# EasyEDA_Bench_2021-02-24.net
KiCad netlist of a schematic drawn in EasyEDA
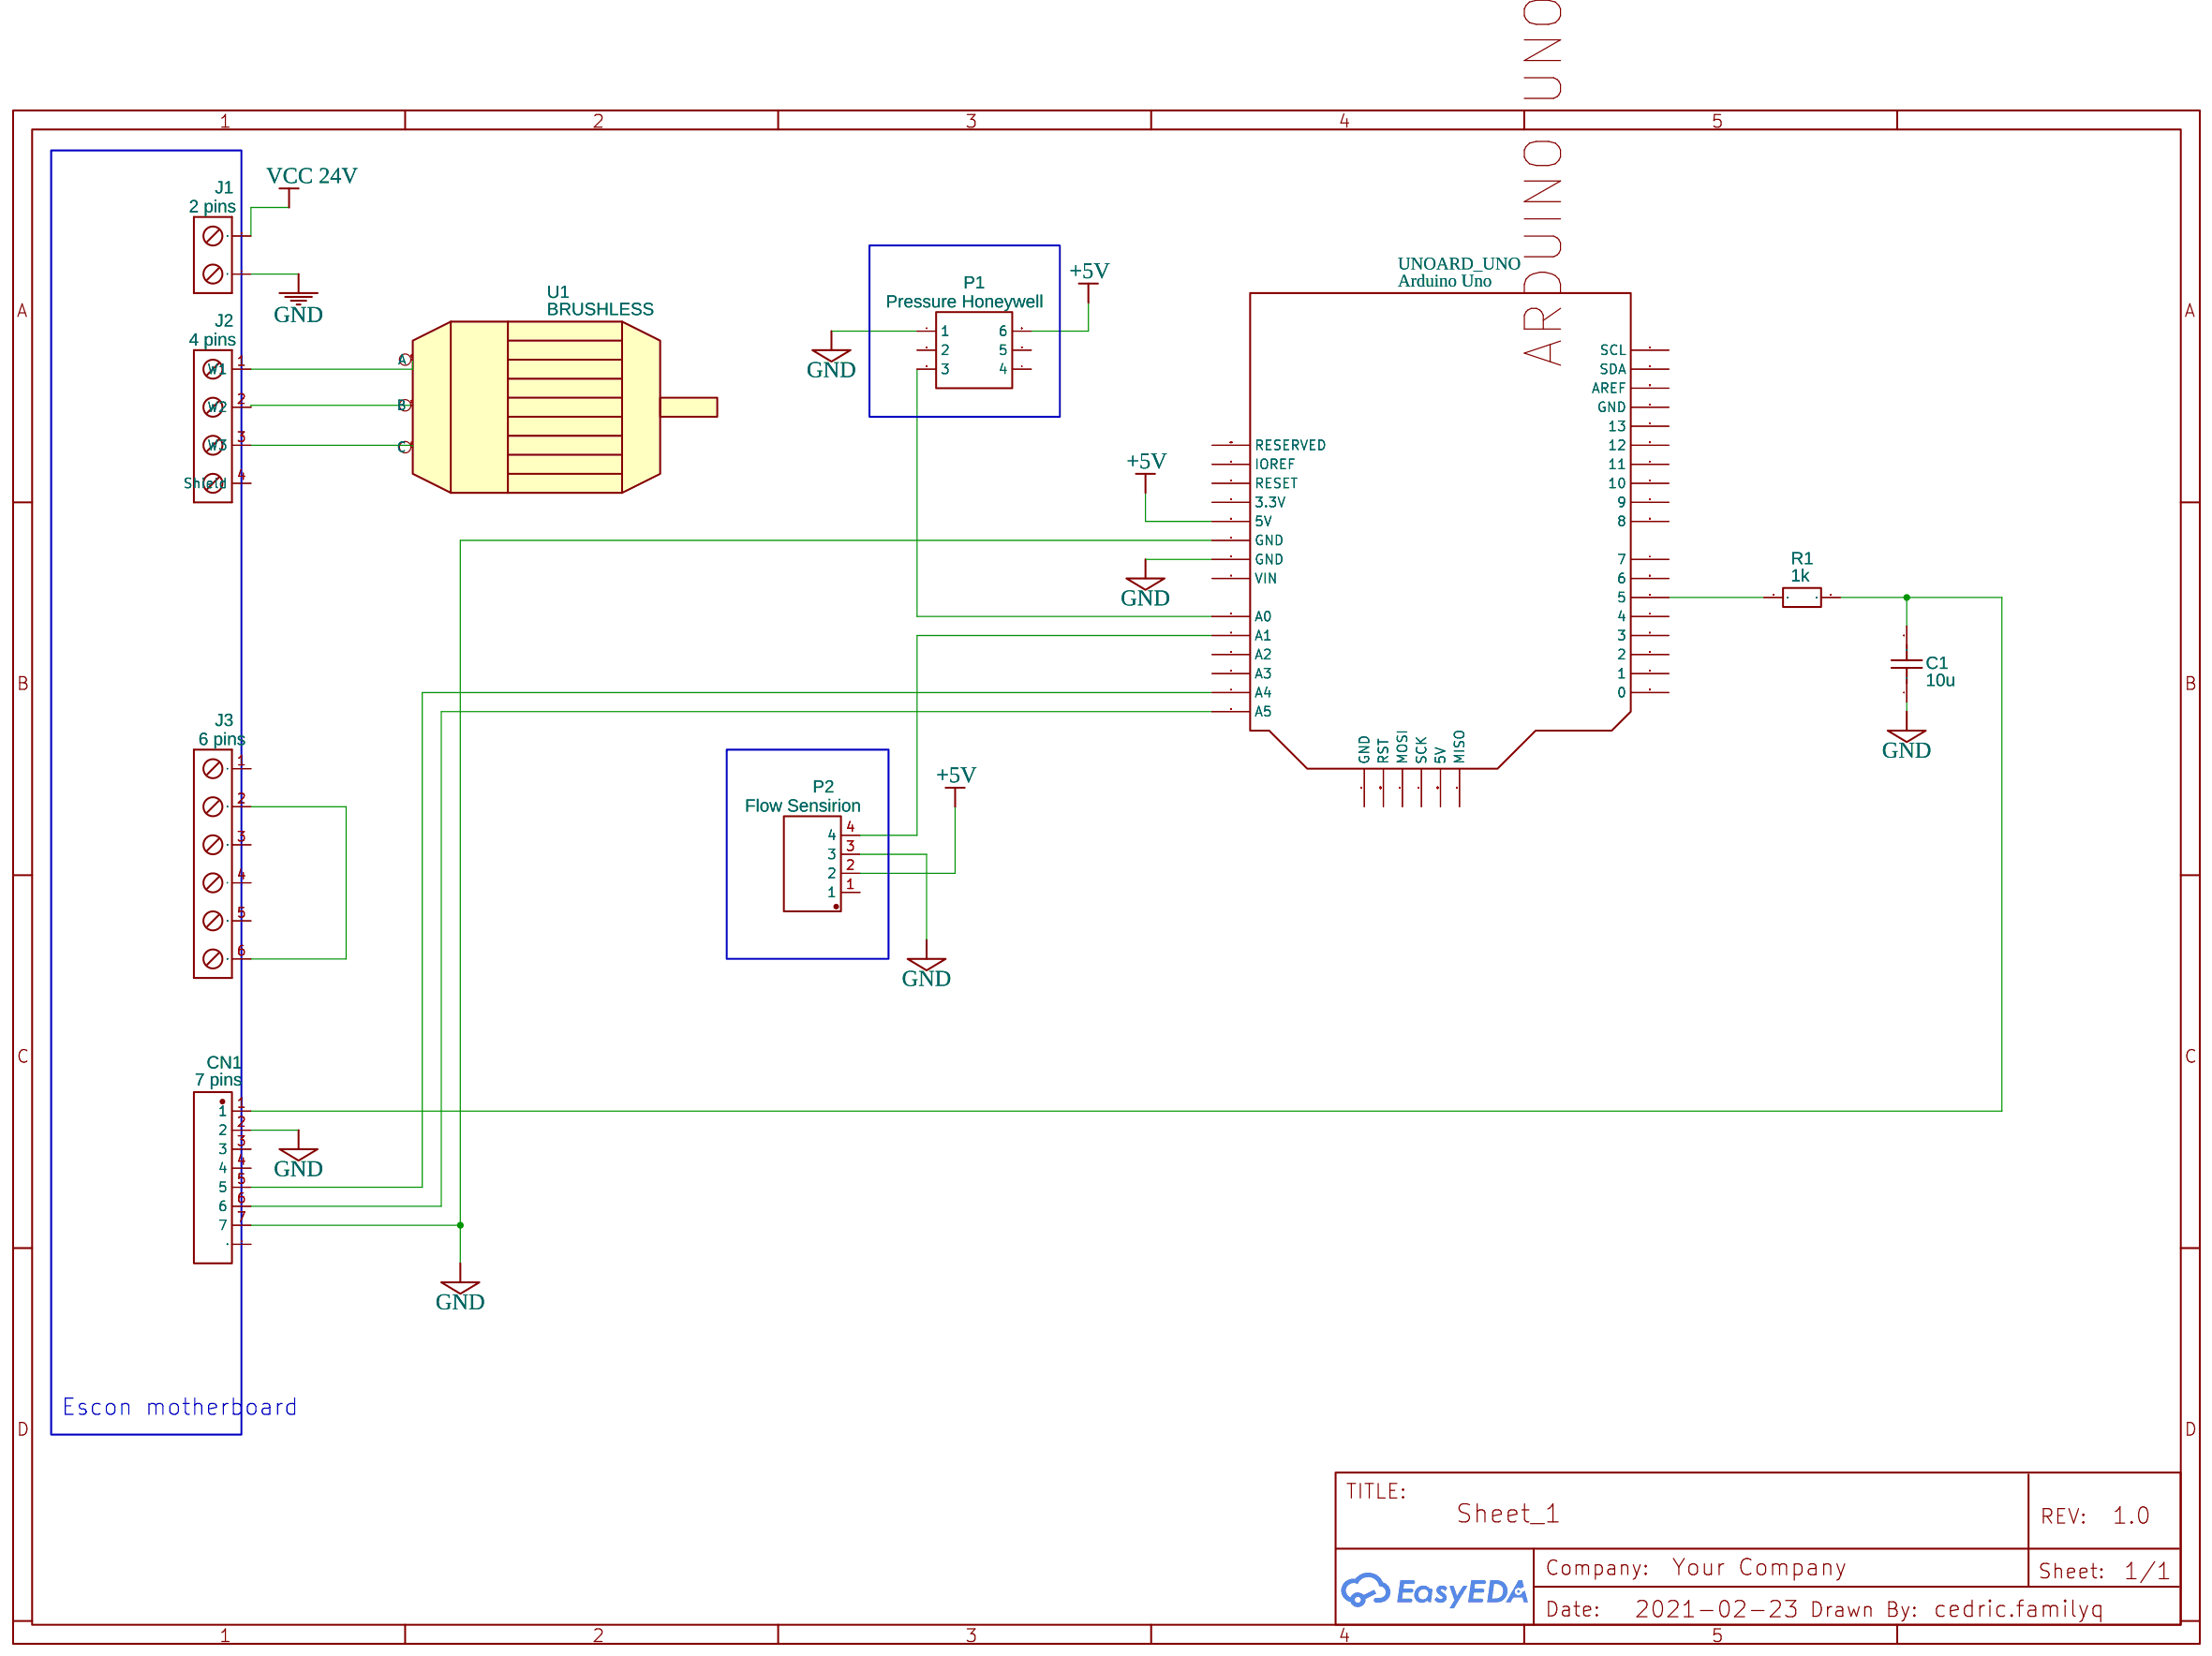
[diagram p0: schematic sheet]

(export (version "E")
  (design (tool "Eeschema 10.0.6"))
  (components
    (comp (ref "C1") (value "10u") (libsource (lib "") (part "C_0603_US")))
    (comp (ref "CN1")
      (value "7 pins")
      (fields
        (field (name "BOM_Manufacturer Part") "B2541CW-8P")
        (field (name "BOM_Supplier Part") "C339803")
      )
      (libsource (lib "") (part "B2541CW-8P"))
    )
    (comp (ref "J1")
      (value "2 pins")
      (fields (field (name "BOM_Manufacturer Part") "?") (field (name "BOM_Supplier Part") "320110031"))
      (libsource (lib "") (part "BORNIER-VIS v2"))
    )
    (comp (ref "J2")
      (value "4 pins")
      (fields (field (name "BOM_Manufacturer Part") "?") (field (name "BOM_Supplier Part") "320110031"))
      (libsource (lib "") (part "BORNIER-VIS-GREEN(4P-5.0)"))
    )
    (comp (ref "J3")
      (value "6 pins")
      (fields (field (name "BOM_Manufacturer Part") "?") (field (name "BOM_Supplier Part") "320110031"))
      (libsource (lib "") (part "BORNIER-VIS-GREEN(6P-5.0)"))
    )
    (comp (ref "P1")
      (value "Pressure Honeywell")
      (fields
        (field (name "BOM_Manufacturer Part") "2X3 2.54mm IDC Box")
        (field (name "BOM_Supplier Part") "C11214")
      )
      (libsource (lib "") (part "HDR-IDC-2.54-2X3P"))
    )
    (comp (ref "P2")
      (value "Flow Sensirion")
      (fields
        (field (name "BOM_Manufacturer Part") "210S-1*4P L=11.6MMGold-plated black")
        (field (name "BOM_Supplier Part") "C124378")
      )
      (libsource (lib "") (part "Header-Male-2.54_1x4_C124378"))
    )
    (comp (ref "R1") (value "1k") (libsource (lib "") (part "R_0603_EU")))
    (comp (ref "U1") (value "BRUSHLESS") (libsource (lib "") (part "BRUSHLESS")))
    (comp (ref "UNOARD_UNO") (value "Arduino Uno") (libsource (lib "") (part "Unknown_750_-570")))
  )
  (nets
    (net (code "1") (name "+5V") (class "Default")
      (node (ref "P1") (pin "6") (pinfunction "6_6") (pintype "unspecified"))
      (node (ref "P2") (pin "2") (pinfunction "2_2") (pintype "unspecified"))
      (node (ref "UNOARD_UNO") (pin "5V") (pinfunction "5V_5V") (pintype "passive"))
    )
    (net (code "2") (name "GND") (class "Default")
      (node (ref "C1") (pin "1") (pinfunction "1_1") (pintype "unspecified"))
      (node (ref "CN1") (pin "2") (pinfunction "2_2") (pintype "unspecified"))
      (node (ref "CN1") (pin "7") (pinfunction "7_7") (pintype "unspecified"))
      (node (ref "J1") (pin "1") (pinfunction "1_1") (pintype "unspecified"))
      (node (ref "P1") (pin "1") (pinfunction "1_1") (pintype "unspecified"))
      (node (ref "P2") (pin "3") (pinfunction "3_3") (pintype "unspecified"))
      (node (ref "UNOARD_UNO") (pin "GND") (pinfunction "GND_GND") (pintype "passive"))
    )
    (net (code "3") (name "Net-(C1-Pad2)") (class "Default")
      (node (ref "C1") (pin "2") (pinfunction "2_2") (pintype "unspecified"))
      (node (ref "CN1") (pin "1") (pinfunction "1_1") (pintype "unspecified"))
      (node (ref "R1") (pin "2") (pinfunction "2_2") (pintype "unspecified"))
    )
    (net (code "4") (name "Net-(CN1-Pad5)") (class "Default")
      (node (ref "CN1") (pin "5") (pinfunction "5_5") (pintype "unspecified"))
      (node (ref "UNOARD_UNO") (pin "A4") (pinfunction "A4_A4") (pintype "bidirectional"))
    )
    (net (code "5") (name "Net-(CN1-Pad6)") (class "Default")
      (node (ref "CN1") (pin "6") (pinfunction "6_6") (pintype "unspecified"))
      (node (ref "UNOARD_UNO") (pin "A5") (pinfunction "A5_A5") (pintype "bidirectional"))
    )
    (net (code "6") (name "Net-(J2-W1)") (class "Default")
      (node (ref "J2") (pin "1") (pinfunction "W1_1") (pintype "unspecified"))
      (node (ref "U1") (pin "1") (pinfunction "A_1") (pintype "unspecified"))
    )
    (net (code "7") (name "Net-(J2-W2)") (class "Default")
      (node (ref "J2") (pin "2") (pinfunction "W2_2") (pintype "unspecified"))
      (node (ref "U1") (pin "2") (pinfunction "B_2") (pintype "unspecified"))
    )
    (net (code "8") (name "Net-(J2-W3)") (class "Default")
      (node (ref "J2") (pin "3") (pinfunction "W3_3") (pintype "unspecified"))
      (node (ref "U1") (pin "3") (pinfunction "C_3") (pintype "unspecified"))
    )
    (net (code "9") (name "Net-(J3-Pad2)") (class "Default")
      (node (ref "J3") (pin "2") (pinfunction "2_2") (pintype "unspecified"))
      (node (ref "J3") (pin "6") (pinfunction "6_6") (pintype "unspecified"))
    )
    (net (code "10") (name "Net-(P1-Pad3)") (class "Default")
      (node (ref "P1") (pin "3") (pinfunction "3_3") (pintype "unspecified"))
      (node (ref "UNOARD_UNO") (pin "A0") (pinfunction "A0_A0") (pintype "bidirectional"))
    )
    (net (code "11") (name "Net-(P2-Pad4)") (class "Default")
      (node (ref "P2") (pin "4") (pinfunction "4_4") (pintype "unspecified"))
      (node (ref "UNOARD_UNO") (pin "A1") (pinfunction "A1_A1") (pintype "bidirectional"))
    )
    (net (code "12") (name "Net-(R1-Pad1)") (class "Default")
      (node (ref "R1") (pin "1") (pinfunction "1_1") (pintype "unspecified"))
      (node (ref "UNOARD_UNO") (pin "5") (pinfunction "5_5") (pintype "bidirectional"))
    )
    (net (code "13") (name "VCC 24V") (class "Default")
      (node (ref "J1") (pin "2") (pinfunction "2_2") (pintype "unspecified"))
    )
    (net (code "14") (name "unconnected-(CN1-Pad3)") (class "Default")
      (node (ref "CN1") (pin "3") (pinfunction "3_3") (pintype "unspecified"))
    )
    (net (code "15") (name "unconnected-(CN1-Pad4)") (class "Default")
      (node (ref "CN1") (pin "4") (pinfunction "4_4") (pintype "unspecified"))
    )
    (net (code "16") (name "unconnected-(CN1-Pad8)") (class "Default")
      (node (ref "CN1") (pin "8") (pinfunction "8_8") (pintype "unspecified"))
    )
    (net (code "17") (name "unconnected-(J2-Shield-Pad4)") (class "Default")
      (node (ref "J2") (pin "4") (pinfunction "Shield_4") (pintype "unspecified"))
    )
    (net (code "18") (name "unconnected-(J3-Pad1)") (class "Default")
      (node (ref "J3") (pin "1") (pinfunction "1_1") (pintype "unspecified"))
    )
    (net (code "19") (name "unconnected-(J3-Pad3)") (class "Default")
      (node (ref "J3") (pin "3") (pinfunction "3_3") (pintype "unspecified"))
    )
    (net (code "20") (name "unconnected-(J3-Pad4)") (class "Default")
      (node (ref "J3") (pin "4") (pinfunction "4_4") (pintype "unspecified"))
    )
    (net (code "21") (name "unconnected-(J3-Pad5)") (class "Default")
      (node (ref "J3") (pin "5") (pinfunction "5_5") (pintype "unspecified"))
    )
    (net (code "22") (name "unconnected-(P1-Pad2)") (class "Default")
      (node (ref "P1") (pin "2") (pinfunction "2_2") (pintype "unspecified"))
    )
    (net (code "23") (name "unconnected-(P1-Pad4)") (class "Default")
      (node (ref "P1") (pin "4") (pinfunction "4_4") (pintype "unspecified"))
    )
    (net (code "24") (name "unconnected-(P1-Pad5)") (class "Default")
      (node (ref "P1") (pin "5") (pinfunction "5_5") (pintype "unspecified"))
    )
    (net (code "25") (name "unconnected-(P2-Pad1)") (class "Default")
      (node (ref "P2") (pin "1") (pinfunction "1_1") (pintype "unspecified"))
    )
    (net (code "26") (name "unconnected-(UNOARD_UNO-5V-Pad5V_ICSP)") (class "Default")
      (node (ref "UNOARD_UNO") (pin "5V_ICSP") (pinfunction "5V_5V_ICSP") (pintype "unspecified"))
    )
    (net (code "27") (name "unconnected-(UNOARD_UNO-Pad0)") (class "Default")
      (node (ref "UNOARD_UNO") (pin "0") (pinfunction "0_0") (pintype "bidirectional"))
    )
    (net (code "28") (name "unconnected-(UNOARD_UNO-Pad1)") (class "Default")
      (node (ref "UNOARD_UNO") (pin "1") (pinfunction "1_1") (pintype "bidirectional"))
    )
    (net (code "29") (name "unconnected-(UNOARD_UNO-Pad2)") (class "Default")
      (node (ref "UNOARD_UNO") (pin "2") (pinfunction "2_2") (pintype "bidirectional"))
    )
    (net (code "30") (name "unconnected-(UNOARD_UNO-Pad3)") (class "Default")
      (node (ref "UNOARD_UNO") (pin "3") (pinfunction "3_3") (pintype "bidirectional"))
    )
    (net (code "31") (name "unconnected-(UNOARD_UNO-Pad3.3V)") (class "Default")
      (node (ref "UNOARD_UNO") (pin "3.3V") (pinfunction "3.3V_3.3V") (pintype "passive"))
    )
    (net (code "32") (name "unconnected-(UNOARD_UNO-Pad4)") (class "Default")
      (node (ref "UNOARD_UNO") (pin "4") (pinfunction "4_4") (pintype "bidirectional"))
    )
    (net (code "33") (name "unconnected-(UNOARD_UNO-Pad6)") (class "Default")
      (node (ref "UNOARD_UNO") (pin "6") (pinfunction "6_6") (pintype "bidirectional"))
    )
    (net (code "34") (name "unconnected-(UNOARD_UNO-Pad7)") (class "Default")
      (node (ref "UNOARD_UNO") (pin "7") (pinfunction "7_7") (pintype "bidirectional"))
    )
    (net (code "35") (name "unconnected-(UNOARD_UNO-Pad8)") (class "Default")
      (node (ref "UNOARD_UNO") (pin "8") (pinfunction "8_8") (pintype "bidirectional"))
    )
    (net (code "36") (name "unconnected-(UNOARD_UNO-Pad9)") (class "Default")
      (node (ref "UNOARD_UNO") (pin "9") (pinfunction "9_9") (pintype "bidirectional"))
    )
    (net (code "37") (name "unconnected-(UNOARD_UNO-Pad10)") (class "Default")
      (node (ref "UNOARD_UNO") (pin "10") (pinfunction "10_10") (pintype "bidirectional"))
    )
    (net (code "38") (name "unconnected-(UNOARD_UNO-Pad11)") (class "Default")
      (node (ref "UNOARD_UNO") (pin "11") (pinfunction "11_11") (pintype "bidirectional"))
    )
    (net (code "39") (name "unconnected-(UNOARD_UNO-Pad12)") (class "Default")
      (node (ref "UNOARD_UNO") (pin "12") (pinfunction "12_12") (pintype "bidirectional"))
    )
    (net (code "40") (name "unconnected-(UNOARD_UNO-Pad13)") (class "Default")
      (node (ref "UNOARD_UNO") (pin "13") (pinfunction "13_13") (pintype "bidirectional"))
    )
    (net (code "41") (name "unconnected-(UNOARD_UNO-PadA2)") (class "Default")
      (node (ref "UNOARD_UNO") (pin "A2") (pinfunction "A2_A2") (pintype "bidirectional"))
    )
    (net (code "42") (name "unconnected-(UNOARD_UNO-PadA3)") (class "Default")
      (node (ref "UNOARD_UNO") (pin "A3") (pinfunction "A3_A3") (pintype "bidirectional"))
    )
    (net (code "43") (name "unconnected-(UNOARD_UNO-PadAREF)") (class "Default")
      (node (ref "UNOARD_UNO") (pin "AREF") (pinfunction "AREF_AREF") (pintype "unspecified"))
    )
    (net (code "44") (name "unconnected-(UNOARD_UNO-PadGND)") (class "Default")
      (node (ref "UNOARD_UNO") (pin "GND") (pinfunction "GND_GND") (pintype "passive"))
    )
    (net (code "45") (name "unconnected-(UNOARD_UNO-PadGND)_1") (class "Default")
      (node (ref "UNOARD_UNO") (pin "GND") (pinfunction "GND_GND") (pintype "unspecified"))
    )
    (net (code "46") (name "unconnected-(UNOARD_UNO-PadIOREF)") (class "Default")
      (node (ref "UNOARD_UNO") (pin "IOREF") (pinfunction "IOREF_IOREF") (pintype "output"))
    )
    (net (code "47") (name "unconnected-(UNOARD_UNO-PadMISO)") (class "Default")
      (node (ref "UNOARD_UNO") (pin "MISO") (pinfunction "MISO_MISO") (pintype "unspecified"))
    )
    (net (code "48") (name "unconnected-(UNOARD_UNO-PadMOSI)") (class "Default")
      (node (ref "UNOARD_UNO") (pin "MOSI") (pinfunction "MOSI_MOSI") (pintype "unspecified"))
    )
    (net (code "49") (name "unconnected-(UNOARD_UNO-PadRESERVED)") (class "Default")
      (node (ref "UNOARD_UNO") (pin "RESERVED") (pinfunction "RESERVED_RESERVED") (pintype "unspecified"))
    )
    (net (code "50") (name "unconnected-(UNOARD_UNO-PadRESET)") (class "Default")
      (node (ref "UNOARD_UNO") (pin "RESET") (pinfunction "RESET_RESET") (pintype "unspecified"))
    )
    (net (code "51") (name "unconnected-(UNOARD_UNO-PadSCK)") (class "Default")
      (node (ref "UNOARD_UNO") (pin "SCK") (pinfunction "SCK_SCK") (pintype "unspecified"))
    )
    (net (code "52") (name "unconnected-(UNOARD_UNO-PadSCL)") (class "Default")
      (node (ref "UNOARD_UNO") (pin "SCL") (pinfunction "SCL_SCL") (pintype "unspecified"))
    )
    (net (code "53") (name "unconnected-(UNOARD_UNO-PadSDA)") (class "Default")
      (node (ref "UNOARD_UNO") (pin "SDA") (pinfunction "SDA_SDA") (pintype "unspecified"))
    )
    (net (code "54") (name "unconnected-(UNOARD_UNO-PadVIN)") (class "Default")
      (node (ref "UNOARD_UNO") (pin "VIN") (pinfunction "VIN_VIN") (pintype "passive"))
    )
    (net (code "55") (name "unconnected-(UNOARD_UNO-RST-PadRESET_ICSP)") (class "Default")
      (node (ref "UNOARD_UNO") (pin "RESET_ICSP") (pinfunction "RST_RESET_ICSP") (pintype "unspecified"))
    )
  )
)
